# MTX_Tap_an_er_V151_Nopoti.net
KiCad netlist of a schematic drawn in EAGLE
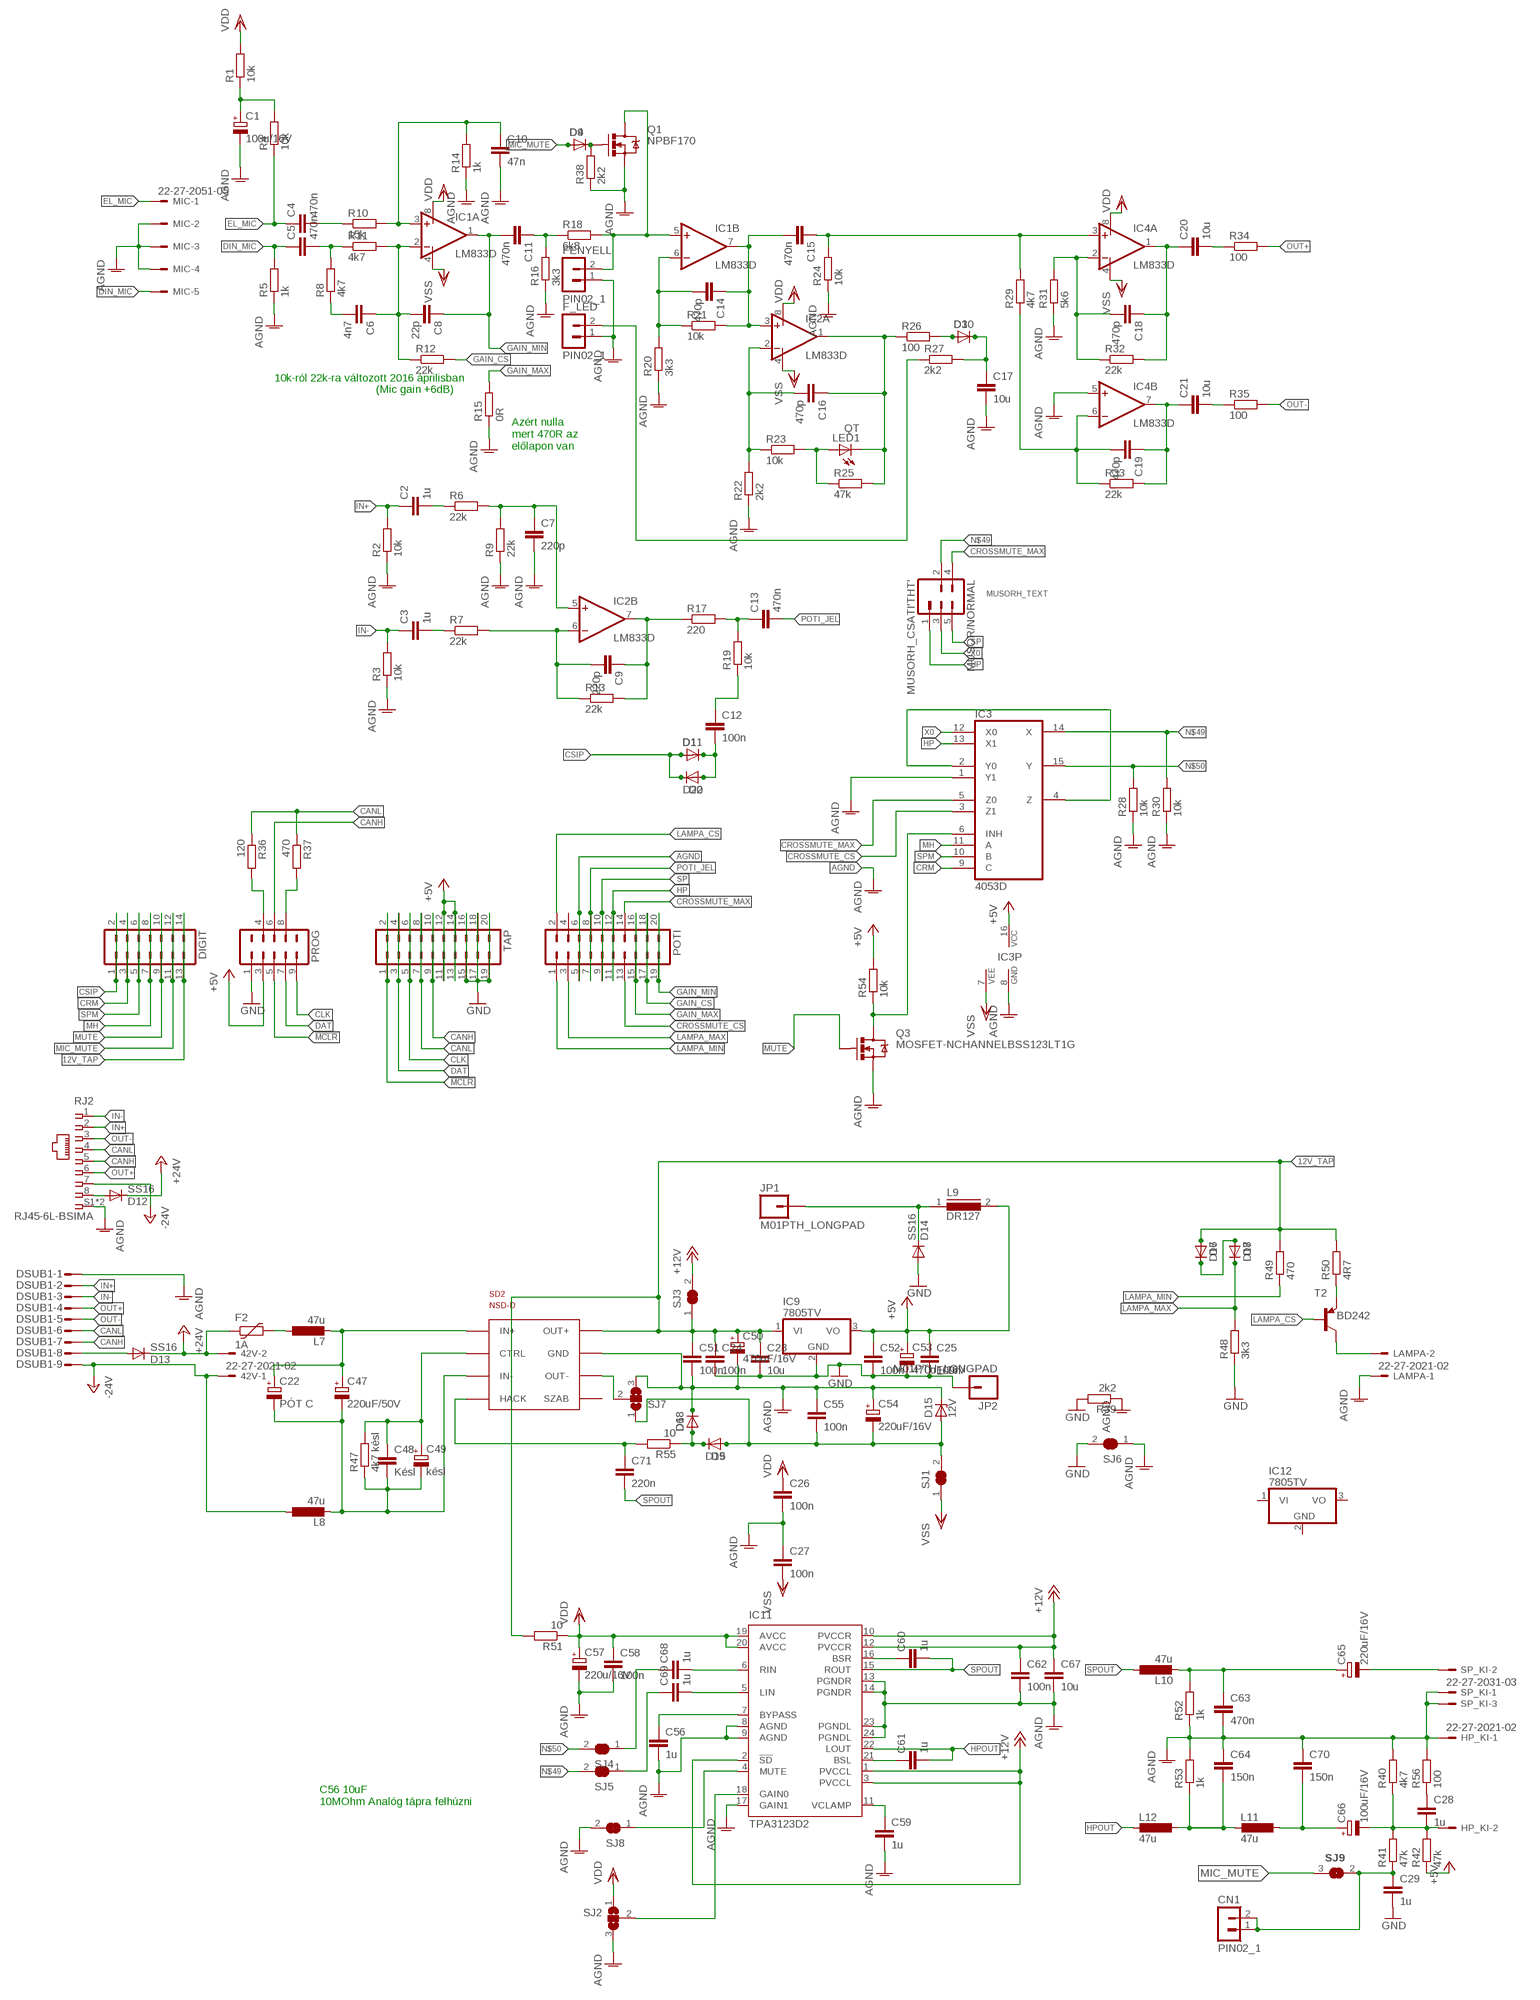
[diagram p0: schematic, sheet 1]

(export (version "E")
  (design (tool "Eeschema 10.0.6"))
  (components
    (comp (ref "42V")
      (value "22-27-2021-02")
      (footprint "eagle-import:6410-02")
      (libsource (lib "eagle-import") (part "22-?-0227-2021"))
    )
    (comp (ref "C1")
      (value "100u/16V")
      (footprint "eagle-import:E2,5-5")
      (libsource (lib "eagle-import") (part "CPOL-EUE2.5-5"))
    )
    (comp (ref "C2")
      (value "1u")
      (footprint "eagle-import:C0805")
      (libsource (lib "eagle-import") (part "C-EUC0805"))
    )
    (comp (ref "C3")
      (value "1u")
      (footprint "eagle-import:C0805")
      (libsource (lib "eagle-import") (part "C-EUC0805"))
    )
    (comp (ref "C4")
      (value "470n")
      (footprint "eagle-import:C0805")
      (libsource (lib "eagle-import") (part "C-EUC0805"))
    )
    (comp (ref "C5")
      (value "470n")
      (footprint "eagle-import:C0805")
      (libsource (lib "eagle-import") (part "C-EUC0805"))
    )
    (comp (ref "C6")
      (value "4n7")
      (footprint "eagle-import:C0805")
      (libsource (lib "eagle-import") (part "C-EUC0805"))
    )
    (comp (ref "C7")
      (value "220p")
      (footprint "eagle-import:C0805")
      (libsource (lib "eagle-import") (part "C-EUC0805"))
    )
    (comp (ref "C8")
      (value "22p")
      (footprint "eagle-import:C0805")
      (libsource (lib "eagle-import") (part "C-EUC0805"))
    )
    (comp (ref "C9")
      (value "220p")
      (footprint "eagle-import:C0805")
      (libsource (lib "eagle-import") (part "C-EUC0805"))
    )
    (comp (ref "C10")
      (value "47n")
      (footprint "eagle-import:C0805")
      (libsource (lib "eagle-import") (part "C-EUC0805"))
    )
    (comp (ref "C11")
      (value "470n")
      (footprint "eagle-import:C0805")
      (libsource (lib "eagle-import") (part "C-EUC0805"))
    )
    (comp (ref "C12")
      (value "100n")
      (footprint "eagle-import:C0805")
      (libsource (lib "eagle-import") (part "C-EUC0805"))
    )
    (comp (ref "C13")
      (value "470n")
      (footprint "eagle-import:C0805")
      (libsource (lib "eagle-import") (part "C-EUC0805"))
    )
    (comp (ref "C14")
      (value "470p")
      (footprint "eagle-import:C0805")
      (libsource (lib "eagle-import") (part "C-EUC0805"))
    )
    (comp (ref "C15")
      (value "470n")
      (footprint "eagle-import:C0805")
      (libsource (lib "eagle-import") (part "C-EUC0805"))
    )
    (comp (ref "C16")
      (value "470p")
      (footprint "eagle-import:C0805")
      (libsource (lib "eagle-import") (part "C-EUC0805"))
    )
    (comp (ref "C17")
      (value "10u")
      (footprint "eagle-import:C0805")
      (libsource (lib "eagle-import") (part "C-EUC0805"))
    )
    (comp (ref "C18")
      (value "470p")
      (footprint "eagle-import:C0805")
      (libsource (lib "eagle-import") (part "C-EUC0805"))
    )
    (comp (ref "C19")
      (value "470p")
      (footprint "eagle-import:C0805")
      (libsource (lib "eagle-import") (part "C-EUC0805"))
    )
    (comp (ref "C20")
      (value "10u")
      (footprint "eagle-import:C0805")
      (libsource (lib "eagle-import") (part "C-EUC0805"))
    )
    (comp (ref "C21")
      (value "10u")
      (footprint "eagle-import:C0805")
      (libsource (lib "eagle-import") (part "C-EUC0805"))
    )
    (comp (ref "C22")
      (value "PÓT C")
      (footprint "eagle-import:E3,5-8")
      (libsource (lib "eagle-import") (part "CPOL-EUE3.5-8"))
    )
    (comp (ref "C23")
      (value "10u")
      (footprint "eagle-import:C0805")
      (libsource (lib "eagle-import") (part "C-EUC0805"))
    )
    (comp (ref "C24")
      (value "100n")
      (footprint "eagle-import:C0805")
      (libsource (lib "eagle-import") (part "C-EUC0805"))
    )
    (comp (ref "C25")
      (value "100n")
      (footprint "eagle-import:C0805")
      (libsource (lib "eagle-import") (part "C-EUC0805"))
    )
    (comp (ref "C26")
      (value "100n")
      (footprint "eagle-import:C0805")
      (libsource (lib "eagle-import") (part "C-EUC0805"))
    )
    (comp (ref "C27")
      (value "100n")
      (footprint "eagle-import:C0805")
      (libsource (lib "eagle-import") (part "C-EUC0805"))
    )
    (comp (ref "C28")
      (value "1u")
      (footprint "eagle-import:C0805")
      (libsource (lib "eagle-import") (part "C-EUC0805"))
    )
    (comp (ref "C29")
      (value "1u")
      (footprint "eagle-import:C0805")
      (libsource (lib "eagle-import") (part "C-EUC0805"))
    )
    (comp (ref "C47")
      (value "220uF/50V")
      (footprint "eagle-import:E3,5-8")
      (libsource (lib "eagle-import") (part "CPOL-EUE3.5-8"))
    )
    (comp (ref "C48")
      (value "Késl")
      (footprint "eagle-import:C0805")
      (libsource (lib "eagle-import") (part "C-EUC0805"))
    )
    (comp (ref "C49")
      (value "késl")
      (footprint "eagle-import:E2,5-5")
      (libsource (lib "eagle-import") (part "CPOL-EUE2.5-5"))
    )
    (comp (ref "C50")
      (value "470uF/16V")
      (footprint "eagle-import:E3,5-8")
      (libsource (lib "eagle-import") (part "CPOL-EUE3.5-8"))
    )
    (comp (ref "C51")
      (value "100n")
      (footprint "eagle-import:C0805")
      (libsource (lib "eagle-import") (part "C-EUC0805"))
    )
    (comp (ref "C52")
      (value "100n")
      (footprint "eagle-import:C0805")
      (libsource (lib "eagle-import") (part "C-EUC0805"))
    )
    (comp (ref "C53")
      (value "470uF/16V")
      (footprint "eagle-import:E3,5-8")
      (libsource (lib "eagle-import") (part "CPOL-EUE3.5-8"))
    )
    (comp (ref "C54")
      (value "220uF/16V")
      (footprint "eagle-import:E2,5-7")
      (libsource (lib "eagle-import") (part "CPOL-EUE2.5-7"))
    )
    (comp (ref "C55")
      (value "100n")
      (footprint "eagle-import:C0805")
      (libsource (lib "eagle-import") (part "C-EUC0805"))
    )
    (comp (ref "C56")
      (value "1u")
      (footprint "eagle-import:C0805")
      (libsource (lib "eagle-import") (part "C-EUC0805"))
    )
    (comp (ref "C57")
      (value "220u/16V")
      (footprint "eagle-import:E2,5-7")
      (libsource (lib "eagle-import") (part "CPOL-EUE2.5-7"))
    )
    (comp (ref "C58")
      (value "100n")
      (footprint "eagle-import:C0805")
      (libsource (lib "eagle-import") (part "C-EUC0805"))
    )
    (comp (ref "C59")
      (value "1u")
      (footprint "eagle-import:C0805")
      (libsource (lib "eagle-import") (part "C-EUC0805"))
    )
    (comp (ref "C60")
      (value "1u")
      (footprint "eagle-import:C0805")
      (libsource (lib "eagle-import") (part "C-EUC0805"))
    )
    (comp (ref "C61")
      (value "1u")
      (footprint "eagle-import:C0805")
      (libsource (lib "eagle-import") (part "C-EUC0805"))
    )
    (comp (ref "C62")
      (value "100n")
      (footprint "eagle-import:C0805")
      (libsource (lib "eagle-import") (part "C-EUC0805"))
    )
    (comp (ref "C63")
      (value "470n")
      (footprint "eagle-import:C0805")
      (libsource (lib "eagle-import") (part "C-EUC0805"))
    )
    (comp (ref "C64")
      (value "150n")
      (footprint "eagle-import:C0805")
      (libsource (lib "eagle-import") (part "C-EUC0805"))
    )
    (comp (ref "C65")
      (value "220uF/16V")
      (footprint "eagle-import:E2,5-7")
      (libsource (lib "eagle-import") (part "CPOL-EUE2.5-7"))
    )
    (comp (ref "C66")
      (value "100uF/16V")
      (footprint "eagle-import:E2,5-6")
      (libsource (lib "eagle-import") (part "CPOL-EUE2.5-6"))
    )
    (comp (ref "C67")
      (value "10u")
      (footprint "eagle-import:C0805")
      (libsource (lib "eagle-import") (part "C-EUC0805"))
    )
    (comp (ref "C68")
      (value "1u")
      (footprint "eagle-import:C0805")
      (libsource (lib "eagle-import") (part "C-EUC0805"))
    )
    (comp (ref "C69")
      (value "1u")
      (footprint "eagle-import:C0805")
      (libsource (lib "eagle-import") (part "C-EUC0805"))
    )
    (comp (ref "C70")
      (value "150n")
      (footprint "eagle-import:C0805")
      (libsource (lib "eagle-import") (part "C-EUC0805"))
    )
    (comp (ref "C71")
      (value "220n")
      (footprint "eagle-import:C0805")
      (libsource (lib "eagle-import") (part "C-EUC0805"))
    )
    (comp (ref "CN1")
      (value "PIN02_1")
      (footprint "eagle-import:PIN02_1")
      (libsource (lib "eagle-import") (part "PIN02_1"))
    )
    (comp (ref "D1")
      (value "1N4148")
      (footprint "eagle-import:DGLASSSMD")
      (libsource (lib "eagle-import") (part "DGLASSMD"))
    )
    (comp (ref "D2")
      (value "1N4148")
      (footprint "eagle-import:DGLASSSMD")
      (libsource (lib "eagle-import") (part "DGLASSMD"))
    )
    (comp (ref "D3")
      (value "1N4148")
      (footprint "eagle-import:DGLASSSMD")
      (libsource (lib "eagle-import") (part "DGLASSMD"))
    )
    (comp (ref "D4")
      (value "1N4148")
      (footprint "eagle-import:DGLASSSMD")
      (libsource (lib "eagle-import") (part "DGLASSMD"))
    )
    (comp (ref "D5")
      (value "D0805")
      (footprint "eagle-import:D0805")
      (libsource (lib "eagle-import") (part "D0805"))
    )
    (comp (ref "D6")
      (value "D0805")
      (footprint "eagle-import:D0805")
      (libsource (lib "eagle-import") (part "D0805"))
    )
    (comp (ref "D7")
      (value "D0805")
      (footprint "eagle-import:D0805")
      (libsource (lib "eagle-import") (part "D0805"))
    )
    (comp (ref "D8")
      (value "D0805")
      (footprint "eagle-import:D0805")
      (libsource (lib "eagle-import") (part "D0805"))
    )
    (comp (ref "D9")
      (value "D0805")
      (footprint "eagle-import:D0805")
      (libsource (lib "eagle-import") (part "D0805"))
    )
    (comp (ref "D10")
      (value "D0805")
      (footprint "eagle-import:D0805")
      (libsource (lib "eagle-import") (part "D0805"))
    )
    (comp (ref "D11")
      (value "D0805")
      (footprint "eagle-import:D0805")
      (libsource (lib "eagle-import") (part "D0805"))
    )
    (comp (ref "D12")
      (value "SS16")
      (footprint "eagle-import:DO-214AC")
      (libsource (lib "eagle-import") (part "SS16"))
    )
    (comp (ref "D13")
      (value "SS16")
      (footprint "eagle-import:DO-214AC")
      (libsource (lib "eagle-import") (part "SS16"))
    )
    (comp (ref "D14")
      (value "SS16")
      (footprint "eagle-import:DO-214AC")
      (libsource (lib "eagle-import") (part "DIODE-DO-214AC"))
    )
    (comp (ref "D15")
      (value "12V")
      (footprint "eagle-import:SOD80C")
      (libsource (lib "eagle-import") (part "ZENER-DIODESOD80C"))
    )
    (comp (ref "D16")
      (value "1N4148")
      (footprint "eagle-import:DGLASSSMD")
      (libsource (lib "eagle-import") (part "DGLASSMD"))
    )
    (comp (ref "D17")
      (value "1N4148")
      (footprint "eagle-import:DGLASSSMD")
      (libsource (lib "eagle-import") (part "DGLASSMD"))
    )
    (comp (ref "D18")
      (value "1N4148")
      (footprint "eagle-import:DGLASSSMD")
      (libsource (lib "eagle-import") (part "DGLASSMD"))
    )
    (comp (ref "D19")
      (value "1N4148")
      (footprint "eagle-import:DGLASSSMD")
      (libsource (lib "eagle-import") (part "DGLASSMD"))
    )
    (comp (ref "D20")
      (value "D0805")
      (footprint "eagle-import:D0805")
      (libsource (lib "eagle-import") (part "D0805"))
    )
    (comp (ref "DIGIT")
      (value "MA07-2")
      (footprint "eagle-import:MA07-2")
      (libsource (lib "eagle-import") (part "MA07-2"))
    )
    (comp (ref "DSUB1")
      (value "M09-182S")
      (footprint "eagle-import:182-009-MALE")
      (libsource (lib "eagle-import") (part "M09?S-182"))
    )
    (comp (ref "F2")
      (value "1A")
      (footprint "eagle-import:PTC1812L")
      (libsource (lib "eagle-import") (part "FUSE_PTC-1812"))
    )
    (comp (ref "FENYELL")
      (value "PIN02_1")
      (footprint "eagle-import:PIN02_1")
      (libsource (lib "eagle-import") (part "PIN02_1"))
    )
    (comp (ref "F_LED")
      (value "PIN02_1")
      (footprint "eagle-import:PIN02_1")
      (libsource (lib "eagle-import") (part "PIN02_1"))
    )
    (comp (ref "HP_KI")
      (value "22-27-2021-02")
      (footprint "eagle-import:6410-02")
      (libsource (lib "eagle-import") (part "22-?-0227-2021"))
    )
    (comp (ref "IC1")
      (value "LM833D")
      (footprint "eagle-import:SO08")
      (libsource (lib "eagle-import") (part "LM833D"))
    )
    (comp (ref "IC2")
      (value "LM833D")
      (footprint "eagle-import:SO08")
      (libsource (lib "eagle-import") (part "LM833D"))
    )
    (comp (ref "IC3")
      (value "4053D")
      (footprint "eagle-import:SO16")
      (libsource (lib "eagle-import") (part "4053D"))
    )
    (comp (ref "IC4")
      (value "LM833D")
      (footprint "eagle-import:SO08")
      (libsource (lib "eagle-import") (part "LM833D"))
    )
    (comp (ref "IC9")
      (value "7805TV")
      (footprint "eagle-import:TO220V")
      (libsource (lib "eagle-import") (part "78TV05"))
    )
    (comp (ref "IC11")
      (value "TPA3123D2")
      (footprint "eagle-import:PWP-TSSOP24")
      (fields (field (name "MPN") "TPA3123D2PWP"))
      (libsource (lib "eagle-import") (part "TPA3123D2"))
    )
    (comp (ref "IC12")
      (value "7805TV")
      (footprint "eagle-import:TO220V")
      (libsource (lib "eagle-import") (part "78TV05"))
    )
    (comp (ref "JP1")
      (value "M01PTH_LONGPAD")
      (footprint "eagle-import:1X01_LONGPAD")
      (libsource (lib "eagle-import") (part "M01PTH_LONGPAD"))
    )
    (comp (ref "JP2")
      (value "M01PTH_LONGPAD")
      (footprint "eagle-import:1X01_LONGPAD")
      (libsource (lib "eagle-import") (part "M01PTH_LONGPAD"))
    )
    (comp (ref "L7")
      (value "47u")
      (footprint "eagle-import:PIS2816")
      (libsource (lib "eagle-import") (part "L-EUPIS2816"))
    )
    (comp (ref "L8")
      (value "47u")
      (footprint "eagle-import:PIS2816")
      (libsource (lib "eagle-import") (part "L-EUPIS2816"))
    )
    (comp (ref "L9")
      (value "DR127")
      (footprint "eagle-import:DR127")
      (libsource (lib "eagle-import") (part "DR127"))
    )
    (comp (ref "L10")
      (value "47u")
      (footprint "eagle-import:PIS2816")
      (libsource (lib "eagle-import") (part "L-EUPIS2816"))
    )
    (comp (ref "L11")
      (value "47u")
      (footprint "eagle-import:PIS2816")
      (libsource (lib "eagle-import") (part "L-EUPIS2816"))
    )
    (comp (ref "L12")
      (value "47u")
      (footprint "eagle-import:PIS2816")
      (libsource (lib "eagle-import") (part "L-EUPIS2816"))
    )
    (comp (ref "LAMPA")
      (value "22-27-2021-02")
      (footprint "eagle-import:6410-02")
      (libsource (lib "eagle-import") (part "22-?-0227-2021"))
    )
    (comp (ref "LED1")
      (value "QT")
      (footprint "eagle-import:LED3MM")
      (libsource (lib "eagle-import") (part "LED3MM"))
    )
    (comp (ref "MIC")
      (value "22-27-2051-05")
      (footprint "eagle-import:6410-05")
      (libsource (lib "eagle-import") (part "22-?-0527-2051"))
    )
    (comp (ref "MUSOR/NORMAL")
      (value "MUSORH_CSATI'THT'")
      (footprint "eagle-import:MUSORH_CSATI")
      (libsource (lib "eagle-import") (part "MUSORH_CSATI'THT'"))
    )
    (comp (ref "POTI")
      (value "MA10-2")
      (footprint "eagle-import:MA10-2")
      (libsource (lib "eagle-import") (part "MA10-2"))
    )
    (comp (ref "PROG")
      (value "CN_CANTAN")
      (footprint "eagle-import:CN_CANTAN")
      (libsource (lib "eagle-import") (part "CN_CANTAN"))
    )
    (comp (ref "Q1")
      (value "NPBF170")
      (footprint "eagle-import:SOT23")
      (libsource (lib "eagle-import") (part "MOSFET-NCHANNELBSS138"))
    )
    (comp (ref "Q3")
      (value "MOSFET-NCHANNELBSS123LT1G")
      (footprint "eagle-import:SOT23")
      (libsource (lib "eagle-import") (part "MOSFET-NCHANNELBSS123LT1G"))
    )
    (comp (ref "R1")
      (value "10k")
      (footprint "eagle-import:R0805")
      (libsource (lib "eagle-import") (part "R-EU_R0805"))
    )
    (comp (ref "R2")
      (value "10k")
      (footprint "eagle-import:R0805")
      (libsource (lib "eagle-import") (part "R-EU_R0805"))
    )
    (comp (ref "R3")
      (value "10k")
      (footprint "eagle-import:R0805")
      (libsource (lib "eagle-import") (part "R-EU_R0805"))
    )
    (comp (ref "R4")
      (value "10k")
      (footprint "eagle-import:R0805")
      (libsource (lib "eagle-import") (part "R-EU_R0805"))
    )
    (comp (ref "R5")
      (value "1k")
      (footprint "eagle-import:R0805")
      (libsource (lib "eagle-import") (part "R-EU_R0805"))
    )
    (comp (ref "R6")
      (value "22k")
      (footprint "eagle-import:R0805")
      (libsource (lib "eagle-import") (part "R-EU_R0805"))
    )
    (comp (ref "R7")
      (value "22k")
      (footprint "eagle-import:R0805")
      (libsource (lib "eagle-import") (part "R-EU_R0805"))
    )
    (comp (ref "R8")
      (value "4k7")
      (footprint "eagle-import:R0805")
      (libsource (lib "eagle-import") (part "R-EU_R0805"))
    )
    (comp (ref "R9")
      (value "22k")
      (footprint "eagle-import:R0805")
      (libsource (lib "eagle-import") (part "R-EU_R0805"))
    )
    (comp (ref "R10")
      (value "15k")
      (footprint "eagle-import:R0805")
      (libsource (lib "eagle-import") (part "R-EU_R0805"))
    )
    (comp (ref "R11")
      (value "4k7")
      (footprint "eagle-import:R0805")
      (libsource (lib "eagle-import") (part "R-EU_R0805"))
    )
    (comp (ref "R12")
      (value "22k")
      (footprint "eagle-import:R0805")
      (libsource (lib "eagle-import") (part "R-EU_R0805"))
    )
    (comp (ref "R13")
      (value "22k")
      (footprint "eagle-import:R0805")
      (libsource (lib "eagle-import") (part "R-EU_R0805"))
    )
    (comp (ref "R14")
      (value "1k")
      (footprint "eagle-import:R0805")
      (libsource (lib "eagle-import") (part "R-EU_R0805"))
    )
    (comp (ref "R15")
      (value "0R")
      (footprint "eagle-import:R0805")
      (libsource (lib "eagle-import") (part "R-EU_R0805"))
    )
    (comp (ref "R16")
      (value "3k3")
      (footprint "eagle-import:R0805")
      (libsource (lib "eagle-import") (part "R-EU_R0805"))
    )
    (comp (ref "R17")
      (value "220")
      (footprint "eagle-import:R0805")
      (libsource (lib "eagle-import") (part "R-EU_R0805"))
    )
    (comp (ref "R18")
      (value "6k8")
      (footprint "eagle-import:R0805")
      (libsource (lib "eagle-import") (part "R-EU_R0805"))
    )
    (comp (ref "R19")
      (value "10k")
      (footprint "eagle-import:R0805")
      (libsource (lib "eagle-import") (part "R-EU_R0805"))
    )
    (comp (ref "R20")
      (value "3k3")
      (footprint "eagle-import:R0805")
      (libsource (lib "eagle-import") (part "R-EU_R0805"))
    )
    (comp (ref "R21")
      (value "10k")
      (footprint "eagle-import:R0805")
      (libsource (lib "eagle-import") (part "R-EU_R0805"))
    )
    (comp (ref "R22")
      (value "2k2")
      (footprint "eagle-import:R0805")
      (libsource (lib "eagle-import") (part "R-EU_R0805"))
    )
    (comp (ref "R23")
      (value "10k")
      (footprint "eagle-import:R0805")
      (libsource (lib "eagle-import") (part "R-EU_R0805"))
    )
    (comp (ref "R24")
      (value "10k")
      (footprint "eagle-import:R0805")
      (libsource (lib "eagle-import") (part "R-EU_R0805"))
    )
    (comp (ref "R25")
      (value "47k")
      (footprint "eagle-import:R0805")
      (libsource (lib "eagle-import") (part "R-EU_R0805"))
    )
    (comp (ref "R26")
      (value "100")
      (footprint "eagle-import:R0805")
      (libsource (lib "eagle-import") (part "R-EU_R0805"))
    )
    (comp (ref "R27")
      (value "2k2")
      (footprint "eagle-import:R0805")
      (libsource (lib "eagle-import") (part "R-EU_R0805"))
    )
    (comp (ref "R28")
      (value "10k")
      (footprint "eagle-import:R0805")
      (libsource (lib "eagle-import") (part "R-EU_R0805"))
    )
    (comp (ref "R29")
      (value "4k7")
      (footprint "eagle-import:R0805")
      (libsource (lib "eagle-import") (part "R-EU_R0805"))
    )
    (comp (ref "R30")
      (value "10k")
      (footprint "eagle-import:R0805")
      (libsource (lib "eagle-import") (part "R-EU_R0805"))
    )
    (comp (ref "R31")
      (value "5k6")
      (footprint "eagle-import:R0805")
      (libsource (lib "eagle-import") (part "R-EU_R0805"))
    )
    (comp (ref "R32")
      (value "22k")
      (footprint "eagle-import:R0805")
      (libsource (lib "eagle-import") (part "R-EU_R0805"))
    )
    (comp (ref "R33")
      (value "22k")
      (footprint "eagle-import:R0805")
      (libsource (lib "eagle-import") (part "R-EU_R0805"))
    )
    (comp (ref "R34")
      (value "100")
      (footprint "eagle-import:R0805")
      (libsource (lib "eagle-import") (part "R-EU_R0805"))
    )
    (comp (ref "R35")
      (value "100")
      (footprint "eagle-import:R0805")
      (libsource (lib "eagle-import") (part "R-EU_R0805"))
    )
    (comp (ref "R36")
      (value "120")
      (footprint "eagle-import:R0805")
      (libsource (lib "eagle-import") (part "R-EU_R0805"))
    )
    (comp (ref "R37")
      (value "470")
      (footprint "eagle-import:R0805")
      (libsource (lib "eagle-import") (part "R-EU_R0805"))
    )
    (comp (ref "R38")
      (value "2k2")
      (footprint "eagle-import:R0805")
      (libsource (lib "eagle-import") (part "R-EU_R0805"))
    )
    (comp (ref "R39")
      (value "2k2")
      (footprint "eagle-import:R0805")
      (libsource (lib "eagle-import") (part "R-EU_R0805"))
    )
    (comp (ref "R40")
      (value "4k7")
      (footprint "eagle-import:R0805")
      (libsource (lib "eagle-import") (part "R-EU_R0805"))
    )
    (comp (ref "R41")
      (value "47k")
      (footprint "eagle-import:R0805")
      (libsource (lib "eagle-import") (part "R-EU_R0805"))
    )
    (comp (ref "R42")
      (value "47k")
      (footprint "eagle-import:R0805")
      (libsource (lib "eagle-import") (part "R-EU_R0805"))
    )
    (comp (ref "R47")
      (value "4k7 késl")
      (footprint "eagle-import:R0805")
      (libsource (lib "eagle-import") (part "R-EU_R0805"))
    )
    (comp (ref "R48")
      (value "3k3")
      (footprint "eagle-import:R0805")
      (libsource (lib "eagle-import") (part "R-EU_R0805"))
    )
    (comp (ref "R49")
      (value "470")
      (footprint "eagle-import:R0805")
      (libsource (lib "eagle-import") (part "R-EU_R0805"))
    )
    (comp (ref "R50")
      (value "4R7")
      (footprint "eagle-import:R0805")
      (libsource (lib "eagle-import") (part "R-EU_R0805"))
    )
    (comp (ref "R51")
      (value "10")
      (footprint "eagle-import:R1210")
      (libsource (lib "eagle-import") (part "R-EU_R1210"))
    )
    (comp (ref "R52")
      (value "1k")
      (footprint "eagle-import:R0805")
      (libsource (lib "eagle-import") (part "R-EU_R0805"))
    )
    (comp (ref "R53")
      (value "1k")
      (footprint "eagle-import:R0805")
      (libsource (lib "eagle-import") (part "R-EU_R0805"))
    )
    (comp (ref "R54")
      (value "10k")
      (footprint "eagle-import:R0805")
      (libsource (lib "eagle-import") (part "R-EU_R0805"))
    )
    (comp (ref "R55")
      (value "10")
      (footprint "eagle-import:R0805")
      (libsource (lib "eagle-import") (part "R-EU_R0805"))
    )
    (comp (ref "R56")
      (value "100")
      (footprint "eagle-import:R0805")
      (libsource (lib "eagle-import") (part "R-EU_R0805"))
    )
    (comp (ref "RJ2")
      (value "RJ45-6L-BSIMA")
      (footprint "eagle-import:RJ45")
      (fields (field (name "MPN") "RJ45-6L-B"))
      (libsource (lib "eagle-import") (part "RJ45SIMA-6L-B"))
    )
    (comp (ref "SD2")
      (value "NSD-D")
      (footprint "eagle-import:NSD-D")
      (libsource (lib "eagle-import") (part "NSD-D"))
    )
    (comp (ref "SJ1")
      (value "SOLDERJUMPER_CLOSED")
      (footprint "eagle-import:SOLDERJUMPER_CLOSEDWIRE")
      (libsource (lib "eagle-import") (part "SOLDERJUMPER_CLOSED"))
    )
    (comp (ref "SJ2")
      (value "SJ2WW12")
      (footprint "eagle-import:SJ_2W_12")
      (libsource (lib "eagle-import") (part "SJ2WW12"))
    )
    (comp (ref "SJ3")
      (value "SOLDERJUMPER_CLOSED")
      (footprint "eagle-import:SOLDERJUMPER_CLOSEDWIRE")
      (libsource (lib "eagle-import") (part "SOLDERJUMPER_CLOSED"))
    )
    (comp (ref "SJ4")
      (value "SOLDERJUMPER_CLOSED")
      (footprint "eagle-import:SOLDERJUMPER_CLOSEDWIRE")
      (libsource (lib "eagle-import") (part "SOLDERJUMPER_CLOSED"))
    )
    (comp (ref "SJ5")
      (value "SOLDERJUMPER_CLOSED")
      (footprint "eagle-import:SOLDERJUMPER_CLOSEDWIRE")
      (libsource (lib "eagle-import") (part "SOLDERJUMPER_CLOSED"))
    )
    (comp (ref "SJ6")
      (value "SOLDERJUMPER_CLOSED")
      (footprint "eagle-import:SOLDERJUMPER_CLOSEDWIRE")
      (libsource (lib "eagle-import") (part "SOLDERJUMPER_CLOSED"))
    )
    (comp (ref "SJ7")
      (value "SJ2WW23")
      (footprint "eagle-import:SJ_2W_23")
      (libsource (lib "eagle-import") (part "SJ2WW23"))
    )
    (comp (ref "SJ8")
      (value "SOLDERJUMPER_CLOSED")
      (footprint "eagle-import:SOLDERJUMPER_CLOSEDWIRE")
      (libsource (lib "eagle-import") (part "SOLDERJUMPER_CLOSED"))
    )
    (comp (ref "SJ9") (value "SJ") (footprint "eagle-import:SJ") (libsource (lib "eagle-import") (part "SJ")))
    (comp (ref "SP_KI")
      (value "22-27-2031-03")
      (footprint "eagle-import:6410-03")
      (libsource (lib "eagle-import") (part "22-?-0327-2031"))
    )
    (comp (ref "T2")
      (value "BD242")
      (footprint "eagle-import:TO220V")
      (libsource (lib "eagle-import") (part "-PNP-TO220V"))
    )
    (comp (ref "TAP")
      (value "MA10-2")
      (footprint "eagle-import:MA10-2")
      (libsource (lib "eagle-import") (part "MA10-2"))
    )
    (comp (ref "U$1")
      (value "MUSORH_TEXT")
      (footprint "eagle-import:MUSORH_TEXT")
      (libsource (lib "eagle-import") (part "MUSORH_TEXT"))
    )
  )
  (nets
    (net (code "1") (name "+5V") (class "Default")
      (node (ref "C25") (pin "1") (pinfunction "1_1") (pintype "passive"))
      (node (ref "C52") (pin "1") (pinfunction "1_1") (pintype "passive"))
      (node (ref "C53") (pin "+") (pinfunction "+_+") (pintype "passive"))
      (node (ref "IC3") (pin "16") (pinfunction "VCC_16") (pintype "power_in"))
      (node (ref "IC9") (pin "3") (pinfunction "VO_3") (pintype "passive"))
      (node (ref "L9") (pin "2") (pinfunction "2_2") (pintype "passive"))
      (node (ref "PROG") (pin "3") (pinfunction "3_3") (pintype "passive"))
      (node (ref "R42") (pin "1") (pinfunction "1_1") (pintype "passive"))
      (node (ref "R54") (pin "2") (pinfunction "2_2") (pintype "passive"))
      (node (ref "TAP") (pin "11") (pinfunction "11_11") (pintype "passive"))
      (node (ref "TAP") (pin "12") (pinfunction "12_12") (pintype "passive"))
      (node (ref "TAP") (pin "13") (pinfunction "13_13") (pintype "passive"))
      (node (ref "TAP") (pin "14") (pinfunction "14_14") (pintype "passive"))
    )
    (net (code "2") (name "+12V") (class "Default")
      (node (ref "C62") (pin "1") (pinfunction "1_1") (pintype "passive"))
      (node (ref "C67") (pin "1") (pinfunction "1_1") (pintype "passive"))
      (node (ref "IC11") (pin "1") (pinfunction "PVCCL_1") (pintype "input"))
      (node (ref "IC11") (pin "10") (pinfunction "PVCCR_10") (pintype "input"))
      (node (ref "IC11") (pin "12") (pinfunction "PVCCR_12") (pintype "input"))
      (node (ref "IC11") (pin "2") (pinfunction "~{SD}_2") (pintype "input"))
      (node (ref "IC11") (pin "3") (pinfunction "PVCCL_3") (pintype "input"))
      (node (ref "SJ3") (pin "2") (pinfunction "2_2") (pintype "passive"))
    )
    (net (code "3") (name "+24V") (class "Default")
      (node (ref "42V") (pin "2") (pinfunction "S_2") (pintype "passive"))
      (node (ref "D12") (pin "1") (pinfunction "C_1") (pintype "passive"))
      (node (ref "D13") (pin "1") (pinfunction "C_1") (pintype "passive"))
      (node (ref "F2") (pin "1") (pinfunction "1_1") (pintype "passive"))
    )
    (net (code "4") (name "-24V") (class "Default")
      (node (ref "42V") (pin "1") (pinfunction "S_1") (pintype "passive"))
      (node (ref "DSUB1") (pin "9") (pinfunction "M_9") (pintype "passive"))
      (node (ref "L8") (pin "1") (pinfunction "1_1") (pintype "passive"))
      (node (ref "RJ2") (pin "7") (pinfunction "7_7") (pintype "passive"))
    )
    (net (code "5") (name "/~{MCLR}") (class "Default")
      (node (ref "PROG") (pin "5") (pinfunction "5_5") (pintype "passive"))
      (node (ref "TAP") (pin "1") (pinfunction "1_1") (pintype "passive"))
      (node (ref "TAP") (pin "2") (pinfunction "2_2") (pintype "passive"))
    )
    (net (code "6") (name "12V_TAP") (class "Default")
      (node (ref "C23") (pin "1") (pinfunction "1_1") (pintype "passive"))
      (node (ref "C24") (pin "1") (pinfunction "1_1") (pintype "passive"))
      (node (ref "C50") (pin "+") (pinfunction "+_+") (pintype "passive"))
      (node (ref "C51") (pin "1") (pinfunction "1_1") (pintype "passive"))
      (node (ref "D16") (pin "P$1") (pinfunction "A_P$1") (pintype "passive"))
      (node (ref "D7") (pin "1") (pinfunction "A_1") (pintype "passive"))
      (node (ref "DIGIT") (pin "13") (pinfunction "13_13") (pintype "passive"))
      (node (ref "DIGIT") (pin "14") (pinfunction "14_14") (pintype "passive"))
      (node (ref "IC9") (pin "1") (pinfunction "VI_1") (pintype "input"))
      (node (ref "R49") (pin "2") (pinfunction "2_2") (pintype "passive"))
      (node (ref "R50") (pin "2") (pinfunction "2_2") (pintype "passive"))
      (node (ref "R51") (pin "2") (pinfunction "2_2") (pintype "passive"))
      (node (ref "SD2") (pin "OUT+") (pinfunction "OUT+_OUT+") (pintype "bidirectional"))
      (node (ref "SJ3") (pin "1") (pinfunction "1_1") (pintype "passive"))
    )
    (net (code "7") (name "AGND") (class "Default")
      (node (ref "C1") (pin "-") (pinfunction "-_-") (pintype "passive"))
      (node (ref "C10") (pin "2") (pinfunction "2_2") (pintype "passive"))
      (node (ref "C17") (pin "2") (pinfunction "2_2") (pintype "passive"))
      (node (ref "C26") (pin "2") (pinfunction "2_2") (pintype "passive"))
      (node (ref "C27") (pin "1") (pinfunction "1_1") (pintype "passive"))
      (node (ref "C50") (pin "-") (pinfunction "-_-") (pintype "passive"))
      (node (ref "C51") (pin "2") (pinfunction "2_2") (pintype "passive"))
      (node (ref "C54") (pin "+") (pinfunction "+_+") (pintype "passive"))
      (node (ref "C55") (pin "1") (pinfunction "1_1") (pintype "passive"))
      (node (ref "C56") (pin "2") (pinfunction "2_2") (pintype "passive"))
      (node (ref "C57") (pin "-") (pinfunction "-_-") (pintype "passive"))
      (node (ref "C58") (pin "2") (pinfunction "2_2") (pintype "passive"))
      (node (ref "C59") (pin "2") (pinfunction "2_2") (pintype "passive"))
      (node (ref "C62") (pin "2") (pinfunction "2_2") (pintype "passive"))
      (node (ref "C63") (pin "2") (pinfunction "2_2") (pintype "passive"))
      (node (ref "C64") (pin "1") (pinfunction "1_1") (pintype "passive"))
      (node (ref "C67") (pin "2") (pinfunction "2_2") (pintype "passive"))
      (node (ref "C7") (pin "2") (pinfunction "2_2") (pintype "passive"))
      (node (ref "C70") (pin "1") (pinfunction "1_1") (pintype "passive"))
      (node (ref "D15") (pin "C") (pinfunction "C_C") (pintype "passive"))
      (node (ref "D18") (pin "P$2") (pinfunction "C_P$2") (pintype "passive"))
      (node (ref "D6") (pin "2") (pinfunction "C_2") (pintype "passive"))
      (node (ref "DSUB1") (pin "1") (pinfunction "M_1") (pintype "passive"))
      (node (ref "FENYELL") (pin "1") (pinfunction "1_1") (pintype "passive"))
      (node (ref "F_LED") (pin "1") (pinfunction "1_1") (pintype "passive"))
      (node (ref "HP_KI") (pin "1") (pinfunction "S_1") (pintype "passive"))
      (node (ref "IC11") (pin "13") (pinfunction "PGNDR_13") (pintype "input"))
      (node (ref "IC11") (pin "14") (pinfunction "PGNDR_14") (pintype "input"))
      (node (ref "IC11") (pin "17") (pinfunction "GAIN1_17") (pintype "input"))
      (node (ref "IC11") (pin "23") (pinfunction "PGNDL_23") (pintype "input"))
      (node (ref "IC11") (pin "24") (pinfunction "PGNDL_24") (pintype "input"))
      (node (ref "IC11") (pin "8") (pinfunction "AGND_8") (pintype "input"))
      (node (ref "IC11") (pin "9") (pinfunction "AGND_9") (pintype "input"))
      (node (ref "IC3") (pin "1") (pinfunction "Y1_1") (pintype "bidirectional"))
      (node (ref "IC3") (pin "8") (pinfunction "GND_8") (pintype "power_in"))
      (node (ref "IC4") (pin "5") (pinfunction "+IN_5") (pintype "input"))
      (node (ref "LAMPA") (pin "1") (pinfunction "S_1") (pintype "passive"))
      (node (ref "MIC") (pin "2") (pinfunction "S_2") (pintype "passive"))
      (node (ref "MIC") (pin "3") (pinfunction "S_3") (pintype "passive"))
      (node (ref "MIC") (pin "4") (pinfunction "S_4") (pintype "passive"))
      (node (ref "POTI") (pin "5") (pinfunction "5_5") (pintype "passive"))
      (node (ref "POTI") (pin "6") (pinfunction "6_6") (pintype "passive"))
      (node (ref "Q1") (pin "2") (pinfunction "S_2") (pintype "passive"))
      (node (ref "Q3") (pin "2") (pinfunction "S_2") (pintype "passive"))
      (node (ref "R14") (pin "1") (pinfunction "1_1") (pintype "passive"))
      (node (ref "R15") (pin "1") (pinfunction "1_1") (pintype "passive"))
      (node (ref "R16") (pin "1") (pinfunction "1_1") (pintype "passive"))
      (node (ref "R2") (pin "1") (pinfunction "1_1") (pintype "passive"))
      (node (ref "R20") (pin "1") (pinfunction "1_1") (pintype "passive"))
      (node (ref "R22") (pin "1") (pinfunction "1_1") (pintype "passive"))
      (node (ref "R24") (pin "1") (pinfunction "1_1") (pintype "passive"))
      (node (ref "R28") (pin "1") (pinfunction "1_1") (pintype "passive"))
      (node (ref "R3") (pin "1") (pinfunction "1_1") (pintype "passive"))
      (node (ref "R30") (pin "1") (pinfunction "1_1") (pintype "passive"))
      (node (ref "R31") (pin "1") (pinfunction "1_1") (pintype "passive"))
      (node (ref "R38") (pin "1") (pinfunction "1_1") (pintype "passive"))
      (node (ref "R39") (pin "1") (pinfunction "1_1") (pintype "passive"))
      (node (ref "R40") (pin "2") (pinfunction "2_2") (pintype "passive"))
      (node (ref "R5") (pin "1") (pinfunction "1_1") (pintype "passive"))
      (node (ref "R52") (pin "1") (pinfunction "1_1") (pintype "passive"))
      (node (ref "R53") (pin "2") (pinfunction "2_2") (pintype "passive"))
      (node (ref "R56") (pin "2") (pinfunction "2_2") (pintype "passive"))
      (node (ref "R9") (pin "1") (pinfunction "1_1") (pintype "passive"))
      (node (ref "RJ2") (pin "S1") (pinfunction "S_S1") (pintype "passive"))
      (node (ref "RJ2") (pin "S2") (pinfunction "S_S2") (pintype "passive"))
      (node (ref "SD2") (pin "COMMON") (pinfunction "GND_COMMON") (pintype "bidirectional"))
      (node (ref "SJ2") (pin "3") (pinfunction "3_3") (pintype "passive"))
      (node (ref "SJ6") (pin "1") (pinfunction "1_1") (pintype "passive"))
      (node (ref "SJ7") (pin "3") (pinfunction "3_3") (pintype "passive"))
      (node (ref "SJ8") (pin "2") (pinfunction "2_2") (pintype "passive"))
      (node (ref "SP_KI") (pin "1") (pinfunction "S_1") (pintype "passive"))
      (node (ref "SP_KI") (pin "3") (pinfunction "S_3") (pintype "passive"))
    )
    (net (code "8") (name "CANH") (class "Default")
      (node (ref "DSUB1") (pin "7") (pinfunction "M_7") (pintype "passive"))
      (node (ref "PROG") (pin "6") (pinfunction "6_6") (pintype "passive"))
      (node (ref "RJ2") (pin "5") (pinfunction "5_5") (pintype "passive"))
      (node (ref "TAP") (pin "10") (pinfunction "10_10") (pintype "passive"))
      (node (ref "TAP") (pin "9") (pinfunction "9_9") (pintype "passive"))
    )
    (net (code "9") (name "CANL") (class "Default")
      (node (ref "DSUB1") (pin "6") (pinfunction "M_6") (pintype "passive"))
      (node (ref "R36") (pin "1") (pinfunction "1_1") (pintype "passive"))
      (node (ref "R37") (pin "1") (pinfunction "1_1") (pintype "passive"))
      (node (ref "RJ2") (pin "4") (pinfunction "4_4") (pintype "passive"))
      (node (ref "TAP") (pin "7") (pinfunction "7_7") (pintype "passive"))
      (node (ref "TAP") (pin "8") (pinfunction "8_8") (pintype "passive"))
    )
    (net (code "10") (name "CLK") (class "Default")
      (node (ref "PROG") (pin "9") (pinfunction "9_9") (pintype "passive"))
      (node (ref "TAP") (pin "5") (pinfunction "5_5") (pintype "passive"))
      (node (ref "TAP") (pin "6") (pinfunction "6_6") (pintype "passive"))
    )
    (net (code "11") (name "CRM") (class "Default")
      (node (ref "DIGIT") (pin "3") (pinfunction "3_3") (pintype "passive"))
      (node (ref "DIGIT") (pin "4") (pinfunction "4_4") (pintype "passive"))
      (node (ref "IC3") (pin "9") (pinfunction "C_9") (pintype "input"))
    )
    (net (code "12") (name "CROSSMUTE_CS") (class "Default")
      (node (ref "IC3") (pin "3") (pinfunction "Z1_3") (pintype "bidirectional"))
      (node (ref "POTI") (pin "13") (pinfunction "13_13") (pintype "passive"))
    )
    (net (code "13") (name "CROSSMUTE_MAX") (class "Default")
      (node (ref "IC3") (pin "5") (pinfunction "Z0_5") (pintype "bidirectional"))
      (node (ref "MUSOR/NORMAL") (pin "4") (pinfunction "4_4") (pintype "passive"))
      (node (ref "POTI") (pin "14") (pinfunction "14_14") (pintype "passive"))
    )
    (net (code "14") (name "CSIP") (class "Default")
      (node (ref "D1") (pin "P$1") (pinfunction "A_P$1") (pintype "passive"))
      (node (ref "D11") (pin "1") (pinfunction "A_1") (pintype "passive"))
      (node (ref "D2") (pin "P$2") (pinfunction "C_P$2") (pintype "passive"))
      (node (ref "D20") (pin "2") (pinfunction "C_2") (pintype "passive"))
      (node (ref "DIGIT") (pin "1") (pinfunction "1_1") (pintype "passive"))
      (node (ref "DIGIT") (pin "2") (pinfunction "2_2") (pintype "passive"))
    )
    (net (code "15") (name "DAT") (class "Default")
      (node (ref "PROG") (pin "7") (pinfunction "7_7") (pintype "passive"))
      (node (ref "TAP") (pin "3") (pinfunction "3_3") (pintype "passive"))
      (node (ref "TAP") (pin "4") (pinfunction "4_4") (pintype "passive"))
    )
    (net (code "16") (name "DIN_MIC") (class "Default")
      (node (ref "C5") (pin "1") (pinfunction "1_1") (pintype "passive"))
      (node (ref "MIC") (pin "5") (pinfunction "S_5") (pintype "passive"))
      (node (ref "R5") (pin "2") (pinfunction "2_2") (pintype "passive"))
    )
    (net (code "17") (name "EL_MIC") (class "Default")
      (node (ref "C4") (pin "1") (pinfunction "1_1") (pintype "passive"))
      (node (ref "MIC") (pin "1") (pinfunction "S_1") (pintype "passive"))
      (node (ref "R4") (pin "1") (pinfunction "1_1") (pintype "passive"))
    )
    (net (code "18") (name "GAIN_CS") (class "Default")
      (node (ref "POTI") (pin "17") (pinfunction "17_17") (pintype "passive"))
      (node (ref "POTI") (pin "18") (pinfunction "18_18") (pintype "passive"))
      (node (ref "R12") (pin "2") (pinfunction "2_2") (pintype "passive"))
    )
    (net (code "19") (name "GAIN_MAX") (class "Default")
      (node (ref "POTI") (pin "15") (pinfunction "15_15") (pintype "passive"))
      (node (ref "POTI") (pin "16") (pinfunction "16_16") (pintype "passive"))
      (node (ref "R15") (pin "2") (pinfunction "2_2") (pintype "passive"))
    )
    (net (code "20") (name "GAIN_MIN") (class "Default")
      (node (ref "C11") (pin "2") (pinfunction "2_2") (pintype "passive"))
      (node (ref "C8") (pin "1") (pinfunction "1_1") (pintype "passive"))
      (node (ref "IC1") (pin "1") (pinfunction "OUT_1") (pintype "output"))
      (node (ref "POTI") (pin "19") (pinfunction "19_19") (pintype "passive"))
      (node (ref "POTI") (pin "20") (pinfunction "20_20") (pintype "passive"))
    )
    (net (code "21") (name "GND") (class "Default")
      (node (ref "C23") (pin "2") (pinfunction "2_2") (pintype "passive"))
      (node (ref "C24") (pin "2") (pinfunction "2_2") (pintype "passive"))
      (node (ref "C25") (pin "2") (pinfunction "2_2") (pintype "passive"))
      (node (ref "C29") (pin "2") (pinfunction "2_2") (pintype "passive"))
      (node (ref "C52") (pin "2") (pinfunction "2_2") (pintype "passive"))
      (node (ref "C53") (pin "-") (pinfunction "-_-") (pintype "passive"))
      (node (ref "D14") (pin "2") (pinfunction "A_2") (pintype "passive"))
      (node (ref "IC9") (pin "2") (pinfunction "GND_2") (pintype "passive"))
      (node (ref "JP2") (pin "1") (pinfunction "1_1") (pintype "passive"))
      (node (ref "PROG") (pin "1") (pinfunction "1_1") (pintype "passive"))
      (node (ref "R39") (pin "2") (pinfunction "2_2") (pintype "passive"))
      (node (ref "R48") (pin "1") (pinfunction "1_1") (pintype "passive"))
      (node (ref "SJ6") (pin "2") (pinfunction "2_2") (pintype "passive"))
      (node (ref "TAP") (pin "15") (pinfunction "15_15") (pintype "passive"))
      (node (ref "TAP") (pin "16") (pinfunction "16_16") (pintype "passive"))
      (node (ref "TAP") (pin "17") (pinfunction "17_17") (pintype "passive"))
      (node (ref "TAP") (pin "18") (pinfunction "18_18") (pintype "passive"))
      (node (ref "TAP") (pin "19") (pinfunction "19_19") (pintype "passive"))
      (node (ref "TAP") (pin "20") (pinfunction "20_20") (pintype "passive"))
    )
    (net (code "22") (name "HP") (class "Default")
      (node (ref "IC3") (pin "13") (pinfunction "X1_13") (pintype "bidirectional"))
      (node (ref "MUSOR/NORMAL") (pin "1") (pinfunction "1_1") (pintype "passive"))
      (node (ref "POTI") (pin "11") (pinfunction "11_11") (pintype "passive"))
      (node (ref "POTI") (pin "12") (pinfunction "12_12") (pintype "passive"))
    )
    (net (code "23") (name "HPOUT") (class "Default")
      (node (ref "C61") (pin "2") (pinfunction "2_2") (pintype "passive"))
      (node (ref "IC11") (pin "22") (pinfunction "LOUT_22") (pintype "output"))
      (node (ref "L12") (pin "2") (pinfunction "2_2") (pintype "passive"))
    )
    (net (code "24") (name "IN+") (class "Default")
      (node (ref "C2") (pin "1") (pinfunction "1_1") (pintype "passive"))
      (node (ref "DSUB1") (pin "2") (pinfunction "M_2") (pintype "passive"))
      (node (ref "R2") (pin "2") (pinfunction "2_2") (pintype "passive"))
      (node (ref "RJ2") (pin "2") (pinfunction "2_2") (pintype "passive"))
    )
    (net (code "25") (name "IN-") (class "Default")
      (node (ref "C3") (pin "1") (pinfunction "1_1") (pintype "passive"))
      (node (ref "DSUB1") (pin "3") (pinfunction "M_3") (pintype "passive"))
      (node (ref "R3") (pin "2") (pinfunction "2_2") (pintype "passive"))
      (node (ref "RJ2") (pin "1") (pinfunction "1_1") (pintype "passive"))
    )
    (net (code "26") (name "LAMPA_CS") (class "Default")
      (node (ref "POTI") (pin "2") (pinfunction "2_2") (pintype "passive"))
      (node (ref "T2") (pin "1") (pinfunction "B_1") (pintype "passive"))
    )
    (net (code "27") (name "LAMPA_MAX") (class "Default")
      (node (ref "D17") (pin "P$2") (pinfunction "C_P$2") (pintype "passive"))
      (node (ref "D8") (pin "2") (pinfunction "C_2") (pintype "passive"))
      (node (ref "POTI") (pin "3") (pinfunction "3_3") (pintype "passive"))
      (node (ref "R48") (pin "2") (pinfunction "2_2") (pintype "passive"))
    )
    (net (code "28") (name "LAMPA_MIN") (class "Default")
      (node (ref "POTI") (pin "1") (pinfunction "1_1") (pintype "passive"))
      (node (ref "R49") (pin "1") (pinfunction "1_1") (pintype "passive"))
    )
    (net (code "29") (name "MH") (class "Default")
      (node (ref "DIGIT") (pin "7") (pinfunction "7_7") (pintype "passive"))
      (node (ref "DIGIT") (pin "8") (pinfunction "8_8") (pintype "passive"))
      (node (ref "IC3") (pin "11") (pinfunction "A_11") (pintype "input"))
    )
    (net (code "30") (name "MIC_MUTE") (class "Default")
      (node (ref "D4") (pin "P$1") (pinfunction "A_P$1") (pintype "passive"))
      (node (ref "D9") (pin "1") (pinfunction "A_1") (pintype "passive"))
      (node (ref "DIGIT") (pin "11") (pinfunction "11_11") (pintype "passive"))
      (node (ref "DIGIT") (pin "12") (pinfunction "12_12") (pintype "passive"))
      (node (ref "SJ9") (pin "3") (pinfunction "1_3") (pintype "passive"))
    )
    (net (code "31") (name "MUTE") (class "Default")
      (node (ref "DIGIT") (pin "10") (pinfunction "10_10") (pintype "passive"))
      (node (ref "DIGIT") (pin "9") (pinfunction "9_9") (pintype "passive"))
      (node (ref "Q3") (pin "1") (pinfunction "G_1") (pintype "passive"))
    )
    (net (code "32") (name "N$49") (class "Default")
      (node (ref "IC3") (pin "14") (pinfunction "X_14") (pintype "bidirectional"))
      (node (ref "MUSOR/NORMAL") (pin "2") (pinfunction "2_2") (pintype "passive"))
      (node (ref "R30") (pin "2") (pinfunction "2_2") (pintype "passive"))
      (node (ref "SJ5") (pin "2") (pinfunction "2_2") (pintype "passive"))
    )
    (net (code "33") (name "N$50") (class "Default")
      (node (ref "IC3") (pin "15") (pinfunction "Y_15") (pintype "bidirectional"))
      (node (ref "R28") (pin "2") (pinfunction "2_2") (pintype "passive"))
      (node (ref "SJ4") (pin "2") (pinfunction "2_2") (pintype "passive"))
    )
    (net (code "34") (name "Net-(C1-Pad+)") (class "Default")
      (node (ref "C1") (pin "+") (pinfunction "+_+") (pintype "passive"))
      (node (ref "R1") (pin "1") (pinfunction "1_1") (pintype "passive"))
      (node (ref "R4") (pin "2") (pinfunction "2_2") (pintype "passive"))
    )
    (net (code "35") (name "Net-(C2-Pad2)") (class "Default")
      (node (ref "C2") (pin "2") (pinfunction "2_2") (pintype "passive"))
      (node (ref "R6") (pin "1") (pinfunction "1_1") (pintype "passive"))
    )
    (net (code "36") (name "Net-(C3-Pad2)") (class "Default")
      (node (ref "C3") (pin "2") (pinfunction "2_2") (pintype "passive"))
      (node (ref "R7") (pin "1") (pinfunction "1_1") (pintype "passive"))
    )
    (net (code "37") (name "Net-(C4-Pad2)") (class "Default")
      (node (ref "C4") (pin "2") (pinfunction "2_2") (pintype "passive"))
      (node (ref "R10") (pin "1") (pinfunction "1_1") (pintype "passive"))
    )
    (net (code "38") (name "Net-(C5-Pad2)") (class "Default")
      (node (ref "C5") (pin "2") (pinfunction "2_2") (pintype "passive"))
      (node (ref "R11") (pin "1") (pinfunction "1_1") (pintype "passive"))
      (node (ref "R8") (pin "2") (pinfunction "2_2") (pintype "passive"))
    )
    (net (code "39") (name "Net-(C6-Pad2)") (class "Default")
      (node (ref "C6") (pin "2") (pinfunction "2_2") (pintype "passive"))
      (node (ref "R8") (pin "1") (pinfunction "1_1") (pintype "passive"))
    )
    (net (code "40") (name "Net-(C11-Pad1)") (class "Default")
      (node (ref "C11") (pin "1") (pinfunction "1_1") (pintype "passive"))
      (node (ref "R16") (pin "2") (pinfunction "2_2") (pintype "passive"))
      (node (ref "R18") (pin "1") (pinfunction "1_1") (pintype "passive"))
    )
    (net (code "41") (name "Net-(C12-Pad1)") (class "Default")
      (node (ref "C12") (pin "1") (pinfunction "1_1") (pintype "passive"))
      (node (ref "R19") (pin "1") (pinfunction "1_1") (pintype "passive"))
    )
    (net (code "42") (name "Net-(C13-Pad1)") (class "Default")
      (node (ref "C13") (pin "1") (pinfunction "1_1") (pintype "passive"))
      (node (ref "R17") (pin "2") (pinfunction "2_2") (pintype "passive"))
      (node (ref "R19") (pin "2") (pinfunction "2_2") (pintype "passive"))
    )
    (net (code "43") (name "Net-(C20-Pad2)") (class "Default")
      (node (ref "C20") (pin "2") (pinfunction "2_2") (pintype "passive"))
      (node (ref "R34") (pin "1") (pinfunction "1_1") (pintype "passive"))
    )
    (net (code "44") (name "Net-(C21-Pad2)") (class "Default")
      (node (ref "C21") (pin "2") (pinfunction "2_2") (pintype "passive"))
      (node (ref "R35") (pin "1") (pinfunction "1_1") (pintype "passive"))
    )
    (net (code "45") (name "Net-(C28-Pad1)") (class "Default")
      (node (ref "C28") (pin "1") (pinfunction "1_1") (pintype "passive"))
      (node (ref "R56") (pin "1") (pinfunction "1_1") (pintype "passive"))
    )
    (net (code "46") (name "Net-(C29-Pad1)") (class "Default")
      (node (ref "C29") (pin "1") (pinfunction "1_1") (pintype "passive"))
      (node (ref "CN1") (pin "1") (pinfunction "1_1") (pintype "passive"))
      (node (ref "CN1") (pin "2") (pinfunction "2_2") (pintype "passive"))
      (node (ref "R41") (pin "1") (pinfunction "1_1") (pintype "passive"))
      (node (ref "SJ9") (pin "2") (pinfunction "2_2") (pintype "passive"))
    )
    (net (code "47") (name "Net-(C63-Pad1)") (class "Default")
      (node (ref "C63") (pin "1") (pinfunction "1_1") (pintype "passive"))
      (node (ref "C65") (pin "+") (pinfunction "+_+") (pintype "passive"))
      (node (ref "L10") (pin "2") (pinfunction "2_2") (pintype "passive"))
      (node (ref "R52") (pin "2") (pinfunction "2_2") (pintype "passive"))
    )
    (net (code "48") (name "Net-(C64-Pad2)") (class "Default")
      (node (ref "C64") (pin "2") (pinfunction "2_2") (pintype "passive"))
      (node (ref "L11") (pin "2") (pinfunction "2_2") (pintype "passive"))
      (node (ref "L12") (pin "1") (pinfunction "1_1") (pintype "passive"))
      (node (ref "R53") (pin "1") (pinfunction "1_1") (pintype "passive"))
    )
    (net (code "49") (name "Net-(C66-Pad+)") (class "Default")
      (node (ref "C66") (pin "+") (pinfunction "+_+") (pintype "passive"))
      (node (ref "C70") (pin "2") (pinfunction "2_2") (pintype "passive"))
      (node (ref "L11") (pin "1") (pinfunction "1_1") (pintype "passive"))
    )
    (net (code "50") (name "Net-(C68-Pad1)") (class "Default")
      (node (ref "C68") (pin "1") (pinfunction "1_1") (pintype "passive"))
      (node (ref "SJ4") (pin "1") (pinfunction "1_1") (pintype "passive"))
    )
    (net (code "51") (name "Net-(C69-Pad1)") (class "Default")
      (node (ref "C69") (pin "1") (pinfunction "1_1") (pintype "passive"))
      (node (ref "SJ5") (pin "1") (pinfunction "1_1") (pintype "passive"))
    )
    (net (code "52") (name "Net-(C71-Pad1)") (class "Default")
      (node (ref "C71") (pin "1") (pinfunction "1_1") (pintype "passive"))
      (node (ref "R55") (pin "2") (pinfunction "2_2") (pintype "passive"))
      (node (ref "SD2") (pin "HACK") (pinfunction "HACK_HACK") (pintype "bidirectional"))
    )
    (net (code "53") (name "Net-(D1-C)") (class "Default")
      (node (ref "C12") (pin "2") (pinfunction "2_2") (pintype "passive"))
      (node (ref "D1") (pin "P$2") (pinfunction "C_P$2") (pintype "passive"))
      (node (ref "D11") (pin "2") (pinfunction "C_2") (pintype "passive"))
      (node (ref "D2") (pin "P$1") (pinfunction "A_P$1") (pintype "passive"))
      (node (ref "D20") (pin "1") (pinfunction "A_1") (pintype "passive"))
    )
    (net (code "54") (name "Net-(D4-C)") (class "Default")
      (node (ref "D4") (pin "P$2") (pinfunction "C_P$2") (pintype "passive"))
      (node (ref "D9") (pin "2") (pinfunction "C_2") (pintype "passive"))
      (node (ref "Q1") (pin "1") (pinfunction "G_1") (pintype "passive"))
      (node (ref "R38") (pin "2") (pinfunction "2_2") (pintype "passive"))
    )
    (net (code "55") (name "Net-(D10-A)") (class "Default")
      (node (ref "D10") (pin "1") (pinfunction "A_1") (pintype "passive"))
      (node (ref "D3") (pin "P$1") (pinfunction "A_P$1") (pintype "passive"))
      (node (ref "R26") (pin "2") (pinfunction "2_2") (pintype "passive"))
    )
    (net (code "56") (name "Net-(D10-C)") (class "Default")
      (node (ref "C17") (pin "1") (pinfunction "1_1") (pintype "passive"))
      (node (ref "D10") (pin "2") (pinfunction "C_2") (pintype "passive"))
      (node (ref "D3") (pin "P$2") (pinfunction "C_P$2") (pintype "passive"))
      (node (ref "R27") (pin "2") (pinfunction "2_2") (pintype "passive"))
    )
    (net (code "57") (name "Net-(D12-A)") (class "Default")
      (node (ref "D12") (pin "2") (pinfunction "A_2") (pintype "passive"))
      (node (ref "RJ2") (pin "8") (pinfunction "8_8") (pintype "passive"))
    )
    (net (code "58") (name "Net-(D13-A)") (class "Default")
      (node (ref "D13") (pin "2") (pinfunction "A_2") (pintype "passive"))
      (node (ref "DSUB1") (pin "8") (pinfunction "M_8") (pintype "passive"))
    )
    (net (code "59") (name "Net-(D14-C)") (class "Default")
      (node (ref "D14") (pin "1") (pinfunction "C_1") (pintype "passive"))
      (node (ref "JP1") (pin "1") (pinfunction "1_1") (pintype "passive"))
      (node (ref "L9") (pin "1") (pinfunction "1_1") (pintype "passive"))
    )
    (net (code "60") (name "Net-(D16-C)") (class "Default")
      (node (ref "D16") (pin "P$2") (pinfunction "C_P$2") (pintype "passive"))
      (node (ref "D17") (pin "P$1") (pinfunction "A_P$1") (pintype "passive"))
      (node (ref "D7") (pin "2") (pinfunction "C_2") (pintype "passive"))
      (node (ref "D8") (pin "1") (pinfunction "A_1") (pintype "passive"))
    )
    (net (code "61") (name "Net-(D18-A)") (class "Default")
      (node (ref "D18") (pin "P$1") (pinfunction "A_P$1") (pintype "passive"))
      (node (ref "D19") (pin "P$2") (pinfunction "C_P$2") (pintype "passive"))
      (node (ref "D5") (pin "2") (pinfunction "C_2") (pintype "passive"))
      (node (ref "D6") (pin "1") (pinfunction "A_1") (pintype "passive"))
      (node (ref "R55") (pin "1") (pinfunction "1_1") (pintype "passive"))
    )
    (net (code "62") (name "Net-(D19-A)") (class "Default")
      (node (ref "C54") (pin "-") (pinfunction "-_-") (pintype "passive"))
      (node (ref "C55") (pin "2") (pinfunction "2_2") (pintype "passive"))
      (node (ref "D15") (pin "A") (pinfunction "A_A") (pintype "passive"))
      (node (ref "D19") (pin "P$1") (pinfunction "A_P$1") (pintype "passive"))
      (node (ref "D5") (pin "1") (pinfunction "A_1") (pintype "passive"))
      (node (ref "SJ1") (pin "2") (pinfunction "2_2") (pintype "passive"))
      (node (ref "SJ7") (pin "1") (pinfunction "1_1") (pintype "passive"))
    )
    (net (code "63") (name "Net-(F2-Pad2)") (class "Default")
      (node (ref "F2") (pin "2") (pinfunction "2_2") (pintype "passive"))
      (node (ref "L7") (pin "1") (pinfunction "1_1") (pintype "passive"))
    )
    (net (code "64") (name "Net-(F_LED-Pad2)") (class "Default")
      (node (ref "F_LED") (pin "2") (pinfunction "2_2") (pintype "passive"))
      (node (ref "R27") (pin "1") (pinfunction "1_1") (pintype "passive"))
    )
    (net (code "65") (name "Net-(HP_KIB-S)") (class "Default")
      (node (ref "C28") (pin "2") (pinfunction "2_2") (pintype "passive"))
      (node (ref "C66") (pin "-") (pinfunction "-_-") (pintype "passive"))
      (node (ref "HP_KI") (pin "2") (pinfunction "S_2") (pintype "passive"))
      (node (ref "R40") (pin "1") (pinfunction "1_1") (pintype "passive"))
      (node (ref "R41") (pin "2") (pinfunction "2_2") (pintype "passive"))
      (node (ref "R42") (pin "2") (pinfunction "2_2") (pintype "passive"))
    )
    (net (code "66") (name "Net-(IC1A-+IN)") (class "Default")
      (node (ref "C10") (pin "1") (pinfunction "1_1") (pintype "passive"))
      (node (ref "IC1") (pin "3") (pinfunction "+IN_3") (pintype "input"))
      (node (ref "R10") (pin "2") (pinfunction "2_2") (pintype "passive"))
      (node (ref "R14") (pin "2") (pinfunction "2_2") (pintype "passive"))
    )
    (net (code "67") (name "Net-(IC1A--IN)") (class "Default")
      (node (ref "C6") (pin "1") (pinfunction "1_1") (pintype "passive"))
      (node (ref "C8") (pin "2") (pinfunction "2_2") (pintype "passive"))
      (node (ref "IC1") (pin "2") (pinfunction "-IN_2") (pintype "input"))
      (node (ref "R11") (pin "2") (pinfunction "2_2") (pintype "passive"))
      (node (ref "R12") (pin "1") (pinfunction "1_1") (pintype "passive"))
    )
    (net (code "68") (name "Net-(IC1B-+IN)") (class "Default")
      (node (ref "FENYELL") (pin "2") (pinfunction "2_2") (pintype "passive"))
      (node (ref "IC1") (pin "5") (pinfunction "+IN_5") (pintype "input"))
      (node (ref "Q1") (pin "3") (pinfunction "D_3") (pintype "passive"))
      (node (ref "R18") (pin "2") (pinfunction "2_2") (pintype "passive"))
    )
    (net (code "69") (name "Net-(IC1B--IN)") (class "Default")
      (node (ref "C14") (pin "2") (pinfunction "2_2") (pintype "passive"))
      (node (ref "IC1") (pin "6") (pinfunction "-IN_6") (pintype "input"))
      (node (ref "R20") (pin "2") (pinfunction "2_2") (pintype "passive"))
      (node (ref "R21") (pin "1") (pinfunction "1_1") (pintype "passive"))
    )
    (net (code "70") (name "Net-(IC1B-OUT)") (class "Default")
      (node (ref "C14") (pin "1") (pinfunction "1_1") (pintype "passive"))
      (node (ref "C15") (pin "2") (pinfunction "2_2") (pintype "passive"))
      (node (ref "IC1") (pin "7") (pinfunction "OUT_7") (pintype "output"))
      (node (ref "IC2") (pin "3") (pinfunction "+IN_3") (pintype "input"))
      (node (ref "R21") (pin "2") (pinfunction "2_2") (pintype "passive"))
    )
    (net (code "71") (name "Net-(IC2A--IN)") (class "Default")
      (node (ref "C16") (pin "2") (pinfunction "2_2") (pintype "passive"))
      (node (ref "IC2") (pin "2") (pinfunction "-IN_2") (pintype "input"))
      (node (ref "R22") (pin "2") (pinfunction "2_2") (pintype "passive"))
      (node (ref "R23") (pin "1") (pinfunction "1_1") (pintype "passive"))
    )
    (net (code "72") (name "Net-(IC2A-OUT)") (class "Default")
      (node (ref "C16") (pin "1") (pinfunction "1_1") (pintype "passive"))
      (node (ref "IC2") (pin "1") (pinfunction "OUT_1") (pintype "output"))
      (node (ref "LED1") (pin "K") (pinfunction "C_K") (pintype "passive"))
      (node (ref "R25") (pin "2") (pinfunction "2_2") (pintype "passive"))
      (node (ref "R26") (pin "1") (pinfunction "1_1") (pintype "passive"))
    )
    (net (code "73") (name "Net-(IC2B-+IN)") (class "Default")
      (node (ref "C7") (pin "1") (pinfunction "1_1") (pintype "passive"))
      (node (ref "IC2") (pin "5") (pinfunction "+IN_5") (pintype "input"))
      (node (ref "R6") (pin "2") (pinfunction "2_2") (pintype "passive"))
      (node (ref "R9") (pin "2") (pinfunction "2_2") (pintype "passive"))
    )
    (net (code "74") (name "Net-(IC2B--IN)") (class "Default")
      (node (ref "C9") (pin "2") (pinfunction "2_2") (pintype "passive"))
      (node (ref "IC2") (pin "6") (pinfunction "-IN_6") (pintype "input"))
      (node (ref "R13") (pin "1") (pinfunction "1_1") (pintype "passive"))
      (node (ref "R7") (pin "2") (pinfunction "2_2") (pintype "passive"))
    )
    (net (code "75") (name "Net-(IC2B-OUT)") (class "Default")
      (node (ref "C9") (pin "1") (pinfunction "1_1") (pintype "passive"))
      (node (ref "IC2") (pin "7") (pinfunction "OUT_7") (pintype "output"))
      (node (ref "R13") (pin "2") (pinfunction "2_2") (pintype "passive"))
      (node (ref "R17") (pin "1") (pinfunction "1_1") (pintype "passive"))
    )
    (net (code "76") (name "Net-(IC3A-INH)") (class "Default")
      (node (ref "IC3") (pin "6") (pinfunction "INH_6") (pintype "input"))
      (node (ref "Q3") (pin "3") (pinfunction "D_3") (pintype "passive"))
      (node (ref "R54") (pin "1") (pinfunction "1_1") (pintype "passive"))
    )
    (net (code "77") (name "Net-(IC3A-Y0)") (class "Default")
      (node (ref "IC3") (pin "2") (pinfunction "Y0_2") (pintype "bidirectional"))
      (node (ref "IC3") (pin "4") (pinfunction "Z_4") (pintype "bidirectional"))
    )
    (net (code "78") (name "Net-(IC4A-+IN)") (class "Default")
      (node (ref "C15") (pin "1") (pinfunction "1_1") (pintype "passive"))
      (node (ref "IC4") (pin "3") (pinfunction "+IN_3") (pintype "input"))
      (node (ref "R24") (pin "2") (pinfunction "2_2") (pintype "passive"))
      (node (ref "R29") (pin "2") (pinfunction "2_2") (pintype "passive"))
    )
    (net (code "79") (name "Net-(IC4A--IN)") (class "Default")
      (node (ref "C18") (pin "2") (pinfunction "2_2") (pintype "passive"))
      (node (ref "IC4") (pin "2") (pinfunction "-IN_2") (pintype "input"))
      (node (ref "R31") (pin "2") (pinfunction "2_2") (pintype "passive"))
      (node (ref "R32") (pin "1") (pinfunction "1_1") (pintype "passive"))
    )
    (net (code "80") (name "Net-(IC4A-OUT)") (class "Default")
      (node (ref "C18") (pin "1") (pinfunction "1_1") (pintype "passive"))
      (node (ref "C20") (pin "1") (pinfunction "1_1") (pintype "passive"))
      (node (ref "IC4") (pin "1") (pinfunction "OUT_1") (pintype "output"))
      (node (ref "R32") (pin "2") (pinfunction "2_2") (pintype "passive"))
    )
    (net (code "81") (name "Net-(IC4B--IN)") (class "Default")
      (node (ref "C19") (pin "2") (pinfunction "2_2") (pintype "passive"))
      (node (ref "IC4") (pin "6") (pinfunction "-IN_6") (pintype "input"))
      (node (ref "R29") (pin "1") (pinfunction "1_1") (pintype "passive"))
      (node (ref "R33") (pin "1") (pinfunction "1_1") (pintype "passive"))
    )
    (net (code "82") (name "Net-(IC4B-OUT)") (class "Default")
      (node (ref "C19") (pin "1") (pinfunction "1_1") (pintype "passive"))
      (node (ref "C21") (pin "1") (pinfunction "1_1") (pintype "passive"))
      (node (ref "IC4") (pin "7") (pinfunction "OUT_7") (pintype "output"))
      (node (ref "R33") (pin "2") (pinfunction "2_2") (pintype "passive"))
    )
    (net (code "83") (name "Net-(IC11-BSL)") (class "Default")
      (node (ref "C61") (pin "1") (pinfunction "1_1") (pintype "passive"))
      (node (ref "IC11") (pin "21") (pinfunction "BSL_21") (pintype "passive"))
    )
    (net (code "84") (name "Net-(IC11-BSR)") (class "Default")
      (node (ref "C60") (pin "1") (pinfunction "1_1") (pintype "passive"))
      (node (ref "IC11") (pin "16") (pinfunction "BSR_16") (pintype "passive"))
    )
    (net (code "85") (name "Net-(IC11-BYPASS)") (class "Default")
      (node (ref "C56") (pin "1") (pinfunction "1_1") (pintype "passive"))
      (node (ref "IC11") (pin "7") (pinfunction "BYPASS_7") (pintype "input"))
    )
    (net (code "86") (name "Net-(IC11-GAIN0)") (class "Default")
      (node (ref "IC11") (pin "18") (pinfunction "GAIN0_18") (pintype "input"))
      (node (ref "SJ2") (pin "2") (pinfunction "2_2") (pintype "passive"))
    )
    (net (code "87") (name "Net-(IC11-LIN)") (class "Default")
      (node (ref "C69") (pin "2") (pinfunction "2_2") (pintype "passive"))
      (node (ref "IC11") (pin "5") (pinfunction "LIN_5") (pintype "input"))
    )
    (net (code "88") (name "Net-(IC11-MUTE)") (class "Default")
      (node (ref "IC11") (pin "4") (pinfunction "MUTE_4") (pintype "input"))
      (node (ref "SJ8") (pin "1") (pinfunction "1_1") (pintype "passive"))
    )
    (net (code "89") (name "Net-(IC11-RIN)") (class "Default")
      (node (ref "C68") (pin "2") (pinfunction "2_2") (pintype "passive"))
      (node (ref "IC11") (pin "6") (pinfunction "RIN_6") (pintype "input"))
    )
    (net (code "90") (name "Net-(IC11-VCLAMP)") (class "Default")
      (node (ref "C59") (pin "1") (pinfunction "1_1") (pintype "passive"))
      (node (ref "IC11") (pin "11") (pinfunction "VCLAMP_11") (pintype "input"))
    )
    (net (code "91") (name "Net-(LAMPAB-S)") (class "Default")
      (node (ref "LAMPA") (pin "2") (pinfunction "S_2") (pintype "passive"))
      (node (ref "T2") (pin "2") (pinfunction "C_2") (pintype "passive"))
    )
    (net (code "92") (name "Net-(LED1-PadA)") (class "Default")
      (node (ref "LED1") (pin "A") (pinfunction "A_A") (pintype "passive"))
      (node (ref "R23") (pin "2") (pinfunction "2_2") (pintype "passive"))
      (node (ref "R25") (pin "1") (pinfunction "1_1") (pintype "passive"))
    )
    (net (code "93") (name "Net-(PROG-Pad4)") (class "Default")
      (node (ref "PROG") (pin "4") (pinfunction "4_4") (pintype "passive"))
      (node (ref "R36") (pin "2") (pinfunction "2_2") (pintype "passive"))
    )
    (net (code "94") (name "Net-(PROG-Pad8)") (class "Default")
      (node (ref "PROG") (pin "8") (pinfunction "8_8") (pintype "passive"))
      (node (ref "R37") (pin "2") (pinfunction "2_2") (pintype "passive"))
    )
    (net (code "95") (name "Net-(SD2-CTRL)") (class "Default")
      (node (ref "C48") (pin "1") (pinfunction "1_1") (pintype "passive"))
      (node (ref "C49") (pin "+") (pinfunction "+_+") (pintype "passive"))
      (node (ref "R47") (pin "2") (pinfunction "2_2") (pintype "passive"))
      (node (ref "SD2") (pin "CONTROL") (pinfunction "CTRL_CONTROL") (pintype "bidirectional"))
    )
    (net (code "96") (name "Net-(SD2-IN+)") (class "Default")
      (node (ref "C22") (pin "+") (pinfunction "+_+") (pintype "passive"))
      (node (ref "C47") (pin "+") (pinfunction "+_+") (pintype "passive"))
      (node (ref "L7") (pin "2") (pinfunction "2_2") (pintype "passive"))
      (node (ref "SD2") (pin "INPUT+") (pinfunction "IN+_INPUT+") (pintype "bidirectional"))
    )
    (net (code "97") (name "Net-(SD2-IN-)") (class "Default")
      (node (ref "C22") (pin "-") (pinfunction "-_-") (pintype "passive"))
      (node (ref "C47") (pin "-") (pinfunction "-_-") (pintype "passive"))
      (node (ref "C48") (pin "2") (pinfunction "2_2") (pintype "passive"))
      (node (ref "C49") (pin "-") (pinfunction "-_-") (pintype "passive"))
      (node (ref "L8") (pin "2") (pinfunction "2_2") (pintype "passive"))
      (node (ref "R47") (pin "1") (pinfunction "1_1") (pintype "passive"))
      (node (ref "SD2") (pin "INPUT-") (pinfunction "IN-_INPUT-") (pintype "bidirectional"))
    )
    (net (code "98") (name "Net-(SD2-PadOUT-)") (class "Default")
      (node (ref "SD2") (pin "OUT-") (pinfunction "OUT-_OUT-") (pintype "bidirectional"))
      (node (ref "SJ7") (pin "2") (pinfunction "2_2") (pintype "passive"))
    )
    (net (code "99") (name "Net-(SP_KIB-S)") (class "Default")
      (node (ref "C65") (pin "-") (pinfunction "-_-") (pintype "passive"))
      (node (ref "SP_KI") (pin "2") (pinfunction "S_2") (pintype "passive"))
    )
    (net (code "100") (name "Net-(T2-E)") (class "Default")
      (node (ref "R50") (pin "1") (pinfunction "1_1") (pintype "passive"))
      (node (ref "T2") (pin "3") (pinfunction "E_3") (pintype "passive"))
    )
    (net (code "101") (name "OUT+") (class "Default")
      (node (ref "DSUB1") (pin "4") (pinfunction "M_4") (pintype "passive"))
      (node (ref "R34") (pin "2") (pinfunction "2_2") (pintype "passive"))
      (node (ref "RJ2") (pin "6") (pinfunction "6_6") (pintype "passive"))
    )
    (net (code "102") (name "OUT-") (class "Default")
      (node (ref "DSUB1") (pin "5") (pinfunction "M_5") (pintype "passive"))
      (node (ref "R35") (pin "2") (pinfunction "2_2") (pintype "passive"))
      (node (ref "RJ2") (pin "3") (pinfunction "3_3") (pintype "passive"))
    )
    (net (code "103") (name "POTI_JEL") (class "Default")
      (node (ref "C13") (pin "2") (pinfunction "2_2") (pintype "passive"))
      (node (ref "POTI") (pin "7") (pinfunction "7_7") (pintype "passive"))
      (node (ref "POTI") (pin "8") (pinfunction "8_8") (pintype "passive"))
    )
    (net (code "104") (name "SP") (class "Default")
      (node (ref "MUSOR/NORMAL") (pin "5") (pinfunction "5_5") (pintype "passive"))
      (node (ref "POTI") (pin "10") (pinfunction "10_10") (pintype "passive"))
      (node (ref "POTI") (pin "9") (pinfunction "9_9") (pintype "passive"))
    )
    (net (code "105") (name "SPM") (class "Default")
      (node (ref "DIGIT") (pin "5") (pinfunction "5_5") (pintype "passive"))
      (node (ref "DIGIT") (pin "6") (pinfunction "6_6") (pintype "passive"))
      (node (ref "IC3") (pin "10") (pinfunction "B_10") (pintype "input"))
    )
    (net (code "106") (name "SPOUT") (class "Default")
      (node (ref "C60") (pin "2") (pinfunction "2_2") (pintype "passive"))
      (node (ref "C71") (pin "2") (pinfunction "2_2") (pintype "passive"))
      (node (ref "IC11") (pin "15") (pinfunction "ROUT_15") (pintype "output"))
      (node (ref "L10") (pin "1") (pinfunction "1_1") (pintype "passive"))
    )
    (net (code "107") (name "VDD") (class "Default")
      (node (ref "C26") (pin "1") (pinfunction "1_1") (pintype "passive"))
      (node (ref "C57") (pin "+") (pinfunction "+_+") (pintype "passive"))
      (node (ref "C58") (pin "1") (pinfunction "1_1") (pintype "passive"))
      (node (ref "IC1") (pin "8") (pinfunction "V+_8") (pintype "power_in"))
      (node (ref "IC11") (pin "19") (pinfunction "AVCC_19") (pintype "input"))
      (node (ref "IC11") (pin "20") (pinfunction "AVCC_20") (pintype "input"))
      (node (ref "IC2") (pin "8") (pinfunction "V+_8") (pintype "power_in"))
      (node (ref "IC4") (pin "8") (pinfunction "V+_8") (pintype "power_in"))
      (node (ref "R1") (pin "2") (pinfunction "2_2") (pintype "passive"))
      (node (ref "R51") (pin "1") (pinfunction "1_1") (pintype "passive"))
      (node (ref "SJ2") (pin "1") (pinfunction "1_1") (pintype "passive"))
    )
    (net (code "108") (name "VSS") (class "Default")
      (node (ref "C27") (pin "2") (pinfunction "2_2") (pintype "passive"))
      (node (ref "IC1") (pin "4") (pinfunction "V-_4") (pintype "power_in"))
      (node (ref "IC2") (pin "4") (pinfunction "V-_4") (pintype "power_in"))
      (node (ref "IC3") (pin "7") (pinfunction "VEE_7") (pintype "power_in"))
      (node (ref "IC4") (pin "4") (pinfunction "V-_4") (pintype "power_in"))
      (node (ref "SJ1") (pin "1") (pinfunction "1_1") (pintype "passive"))
    )
    (net (code "109") (name "X0") (class "Default")
      (node (ref "IC3") (pin "12") (pinfunction "X0_12") (pintype "bidirectional"))
      (node (ref "MUSOR/NORMAL") (pin "3") (pinfunction "3_3") (pintype "passive"))
    )
    (net (code "110") (name "unconnected-(IC12-GND-Pad2)") (class "Default")
      (node (ref "IC12") (pin "2") (pinfunction "GND_2") (pintype "passive"))
    )
    (net (code "111") (name "unconnected-(IC12-VI-Pad1)") (class "Default")
      (node (ref "IC12") (pin "1") (pinfunction "VI_1") (pintype "input"))
    )
    (net (code "112") (name "unconnected-(IC12-VO-Pad3)") (class "Default")
      (node (ref "IC12") (pin "3") (pinfunction "VO_3") (pintype "passive"))
    )
    (net (code "113") (name "unconnected-(POTI-Pad4)") (class "Default")
      (node (ref "POTI") (pin "4") (pinfunction "4_4") (pintype "passive"))
    )
    (net (code "114") (name "unconnected-(SD2-PadSZAB)") (class "Default")
      (node (ref "SD2") (pin "SZAB") (pinfunction "SZAB_SZAB") (pintype "bidirectional"))
    )
  )
)
